# SHT1x.net
KiCad netlist of a schematic drawn in Altium Designer
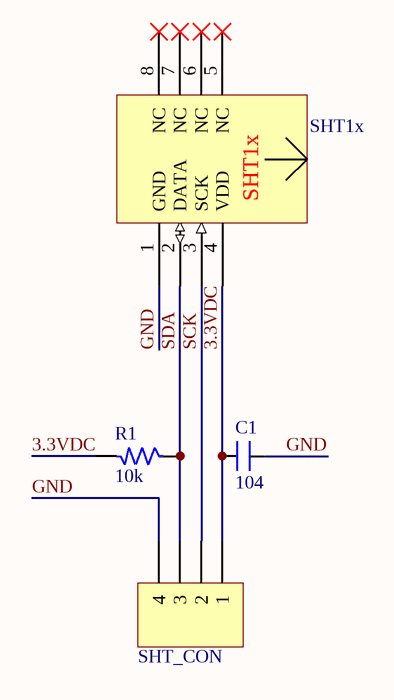
[diagram p0: SHT1x.SchDoc]

(export (version "E")
  (design (tool "Eeschema 10.0.6"))
  (components
    (comp (ref "C1")
      (value "104")
      (footprint "C0805")
      (description "Cap SMD")
      (libsource (lib "syhaunguyen") (part "CM"))
    )
    (comp (ref "R1")
      (value "10k")
      (footprint "C0805")
      (description "Resistor 1/4W")
      (libsource (lib "syhaunguyen") (part "R"))
    )
    (comp (ref "SHT1x") (value "SHT1x") (footprint "SHT1x") (libsource (lib "syhaunguyen") (part "SHT1x")))
    (comp (ref "SHT_CON")
      (value "SHTCON")
      (footprint "HDR1X4")
      (description "Header, 4-Pin")
      (fields (field (name "PUBLISHER") "Altium Limited"))
      (libsource (lib "Miscellaneous Connectors") (part "Header 4"))
    )
  )
  (nets
    (net (code "1") (name "/3.3VDC") (class "Default")
      (node (ref "C1") (pin "2") (pinfunction "2_2") (pintype "passive"))
      (node (ref "R1") (pin "2") (pinfunction "2_2") (pintype "passive"))
      (node (ref "SHT1x") (pin "4") (pinfunction "VDD_4") (pintype "power_in"))
      (node (ref "SHT_CON") (pin "1") (pinfunction "1_1") (pintype "passive"))
    )
    (net (code "2") (name "/GND") (class "Default")
      (node (ref "C1") (pin "1") (pinfunction "1_1") (pintype "passive"))
      (node (ref "SHT1x") (pin "1") (pinfunction "GND_1") (pintype "power_in"))
      (node (ref "SHT_CON") (pin "4") (pinfunction "4_4") (pintype "passive"))
    )
    (net (code "3") (name "/SCK") (class "Default")
      (node (ref "SHT1x") (pin "3") (pinfunction "SCK_3") (pintype "input"))
      (node (ref "SHT_CON") (pin "2") (pinfunction "2_2") (pintype "passive"))
    )
    (net (code "4") (name "/SDA") (class "Default")
      (node (ref "R1") (pin "1") (pinfunction "1_1") (pintype "passive"))
      (node (ref "SHT1x") (pin "2") (pinfunction "DATA_2") (pintype "bidirectional"))
      (node (ref "SHT_CON") (pin "3") (pinfunction "3_3") (pintype "passive"))
    )
    (net (code "5") (name "unconnected-(SHT1x-NC-Pad5)") (class "Default")
      (node (ref "SHT1x") (pin "5") (pinfunction "NC_5") (pintype "passive+no_connect"))
    )
    (net (code "6") (name "unconnected-(SHT1x-NC-Pad6)") (class "Default")
      (node (ref "SHT1x") (pin "6") (pinfunction "NC_6") (pintype "passive+no_connect"))
    )
    (net (code "7") (name "unconnected-(SHT1x-NC-Pad7)") (class "Default")
      (node (ref "SHT1x") (pin "7") (pinfunction "NC_7") (pintype "passive+no_connect"))
    )
    (net (code "8") (name "unconnected-(SHT1x-NC-Pad8)") (class "Default")
      (node (ref "SHT1x") (pin "8") (pinfunction "NC_8") (pintype "passive+no_connect"))
    )
  )
)
